# Populated_PLG_sensor.net
KiCad netlist of a schematic drawn in EAGLE
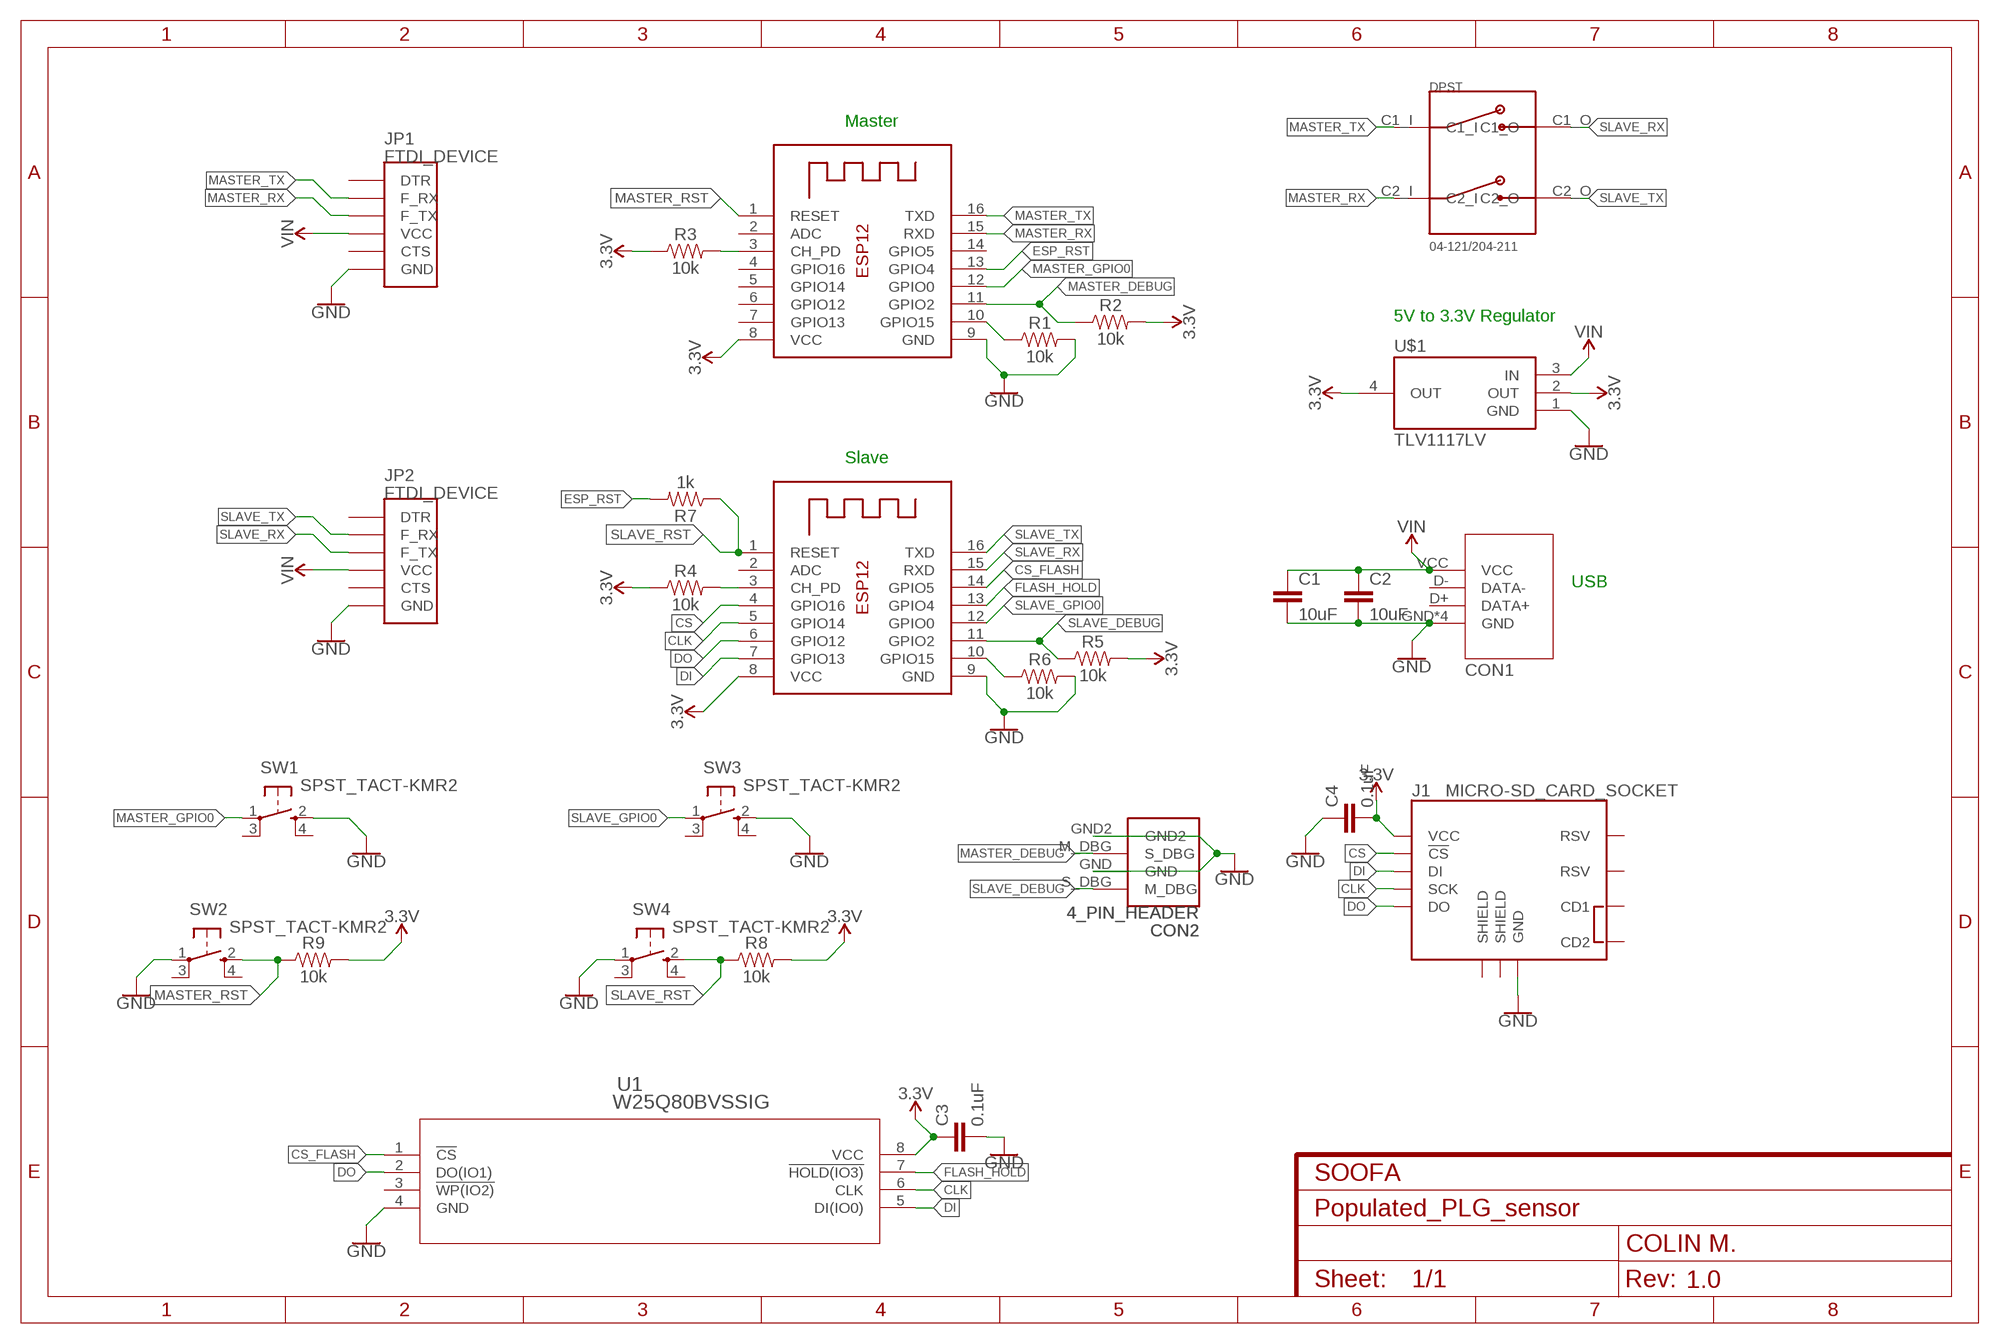
[diagram p0: schematic, sheet 1]

(export (version "E")
  (design (tool "Eeschema 10.0.6"))
  (components
    (comp (ref "C1")
      (value "10uF")
      (footprint "eagle-import:0603")
      (libsource (lib "eagle-import") (part "10UF-0603-6.3V-20%"))
    )
    (comp (ref "C2")
      (value "10uF")
      (footprint "eagle-import:0603")
      (libsource (lib "eagle-import") (part "10UF-0603-6.3V-20%"))
    )
    (comp (ref "C3")
      (value "0.1uF")
      (footprint "eagle-import:0603")
      (libsource (lib "eagle-import") (part "0.1UF-0603-25V-(+80/-20%)"))
    )
    (comp (ref "C4")
      (value "0.1uF")
      (footprint "eagle-import:0603")
      (libsource (lib "eagle-import") (part "0.1UF-0603-25V-(+80/-20%)"))
    )
    (comp (ref "CON1")
      (value "USB_MOLEX_0480372200")
      (footprint "eagle-import:USB_MOLEX_0480372200")
      (libsource (lib "eagle-import") (part "USB_MOLEX_0480372200"))
    )
    (comp (ref "CON2")
      (value "4_PIN_HEADER")
      (footprint "eagle-import:22-23-2041")
      (libsource (lib "eagle-import") (part "4_PIN_HEADER"))
    )
    (comp (ref "DPST1")
      (value "DPST_1POS")
      (footprint "eagle-import:DPST_1POS")
      (libsource (lib "eagle-import") (part "DPST_1POS"))
    )
    (comp (ref "J1")
      (value "MICRO-SD_CARD_SOCKET")
      (footprint "eagle-import:MICRO-SD-SOCKET")
      (libsource (lib "eagle-import") (part "MICRO-SD_CARD_SOCKET"))
    )
    (comp (ref "JP1")
      (value "FTDI_DEVICE")
      (footprint "eagle-import:FTDI_DEVICE_SIDE")
      (libsource (lib "eagle-import") (part "FTDI_DEVICE"))
    )
    (comp (ref "JP2")
      (value "FTDI_DEVICE")
      (footprint "eagle-import:FTDI_DEVICE_SIDE")
      (libsource (lib "eagle-import") (part "FTDI_DEVICE"))
    )
    (comp (ref "R1")
      (value "10k")
      (footprint "eagle-import:0603")
      (libsource (lib "eagle-import") (part "10KOHM-0603-1/10W-1%"))
    )
    (comp (ref "R2")
      (value "10k")
      (footprint "eagle-import:0603")
      (libsource (lib "eagle-import") (part "10KOHM-0603-1/10W-1%"))
    )
    (comp (ref "R3")
      (value "10k")
      (footprint "eagle-import:0603")
      (libsource (lib "eagle-import") (part "10KOHM-0603-1/10W-1%"))
    )
    (comp (ref "R4")
      (value "10k")
      (footprint "eagle-import:0603")
      (libsource (lib "eagle-import") (part "10KOHM-0603-1/10W-1%"))
    )
    (comp (ref "R5")
      (value "10k")
      (footprint "eagle-import:0603")
      (libsource (lib "eagle-import") (part "10KOHM-0603-1/10W-1%"))
    )
    (comp (ref "R6")
      (value "10k")
      (footprint "eagle-import:0603")
      (libsource (lib "eagle-import") (part "10KOHM-0603-1/10W-1%"))
    )
    (comp (ref "R7")
      (value "1k")
      (footprint "eagle-import:0603")
      (libsource (lib "eagle-import") (part "1KOHM-0603-1/10W-1%"))
    )
    (comp (ref "R8")
      (value "10k")
      (footprint "eagle-import:0603")
      (libsource (lib "eagle-import") (part "10KOHM-0603-1/10W-1%"))
    )
    (comp (ref "R9")
      (value "10k")
      (footprint "eagle-import:0603")
      (libsource (lib "eagle-import") (part "10KOHM-0603-1/10W-1%"))
    )
    (comp (ref "SW1")
      (value "SPST_TACT-KMR2")
      (footprint "eagle-import:KMR2")
      (libsource (lib "eagle-import") (part "SPST_TACT-KMR2"))
    )
    (comp (ref "SW2")
      (value "SPST_TACT-KMR2")
      (footprint "eagle-import:KMR2")
      (libsource (lib "eagle-import") (part "SPST_TACT-KMR2"))
    )
    (comp (ref "SW3")
      (value "SPST_TACT-KMR2")
      (footprint "eagle-import:KMR2")
      (libsource (lib "eagle-import") (part "SPST_TACT-KMR2"))
    )
    (comp (ref "SW4")
      (value "SPST_TACT-KMR2")
      (footprint "eagle-import:KMR2")
      (libsource (lib "eagle-import") (part "SPST_TACT-KMR2"))
    )
    (comp (ref "U$1")
      (value "TLV1117LV")
      (footprint "eagle-import:SOT223")
      (libsource (lib "eagle-import") (part "TLV1117LV"))
    )
    (comp (ref "U1")
      (value "W25Q80BVSSIG")
      (footprint "eagle-import:WIN_SS-8")
      (libsource (lib "eagle-import") (part "W25Q80BVSSIG"))
    )
    (comp (ref "X1")
      (value "ESP-12")
      (footprint "eagle-import:ESP-12")
      (libsource (lib "eagle-import") (part "ESP-12"))
    )
    (comp (ref "X2")
      (value "ESP-12")
      (footprint "eagle-import:ESP-12")
      (libsource (lib "eagle-import") (part "ESP-12"))
    )
  )
  (nets
    (net (code "1") (name "3.3V") (class "Default")
      (node (ref "C3") (pin "1") (pinfunction "1_1") (pintype "passive"))
      (node (ref "C4") (pin "2") (pinfunction "2_2") (pintype "passive"))
      (node (ref "J1") (pin "VCC") (pinfunction "VCC_VCC") (pintype "bidirectional"))
      (node (ref "R2") (pin "2") (pinfunction "2_2") (pintype "passive"))
      (node (ref "R3") (pin "1") (pinfunction "1_1") (pintype "passive"))
      (node (ref "R4") (pin "1") (pinfunction "1_1") (pintype "passive"))
      (node (ref "R5") (pin "2") (pinfunction "2_2") (pintype "passive"))
      (node (ref "R8") (pin "2") (pinfunction "2_2") (pintype "passive"))
      (node (ref "R9") (pin "2") (pinfunction "2_2") (pintype "passive"))
      (node (ref "U$1") (pin "2") (pinfunction "OUT_2") (pintype "bidirectional"))
      (node (ref "U$1") (pin "4") (pinfunction "OUT_4") (pintype "bidirectional"))
      (node (ref "U1") (pin "8") (pinfunction "VCC_8") (pintype "power_in"))
      (node (ref "X1") (pin "8") (pinfunction "VCC_8") (pintype "power_in"))
      (node (ref "X2") (pin "8") (pinfunction "VCC_8") (pintype "power_in"))
    )
    (net (code "2") (name "CLK") (class "Default")
      (node (ref "J1") (pin "SCLK") (pinfunction "SCK_SCLK") (pintype "bidirectional"))
      (node (ref "U1") (pin "6") (pinfunction "CLK_6") (pintype "input"))
      (node (ref "X2") (pin "5") (pinfunction "GPIO14_5") (pintype "bidirectional"))
    )
    (net (code "3") (name "CS") (class "Default")
      (node (ref "J1") (pin "CS") (pinfunction "~{CS}_CS") (pintype "bidirectional"))
      (node (ref "X2") (pin "4") (pinfunction "GPIO16_4") (pintype "bidirectional"))
    )
    (net (code "4") (name "CS_FLASH") (class "Default")
      (node (ref "U1") (pin "1") (pinfunction "~{CS}_1") (pintype "input"))
      (node (ref "X2") (pin "14") (pinfunction "GPIO5_14") (pintype "bidirectional"))
    )
    (net (code "5") (name "DI") (class "Default")
      (node (ref "J1") (pin "DI") (pinfunction "DI_DI") (pintype "bidirectional"))
      (node (ref "U1") (pin "5") (pinfunction "DI(IO0)_5") (pintype "bidirectional"))
      (node (ref "X2") (pin "7") (pinfunction "GPIO13_7") (pintype "bidirectional"))
    )
    (net (code "6") (name "DO") (class "Default")
      (node (ref "J1") (pin "DO") (pinfunction "DO_DO") (pintype "bidirectional"))
      (node (ref "U1") (pin "2") (pinfunction "DO(IO1)_2") (pintype "bidirectional"))
      (node (ref "X2") (pin "6") (pinfunction "GPIO12_6") (pintype "bidirectional"))
    )
    (net (code "7") (name "ESP_RST") (class "Default")
      (node (ref "R7") (pin "2") (pinfunction "2_2") (pintype "passive"))
      (node (ref "X1") (pin "13") (pinfunction "GPIO4_13") (pintype "bidirectional"))
    )
    (net (code "8") (name "FLASH_HOLD") (class "Default")
      (node (ref "U1") (pin "7") (pinfunction "~{HOLD(IO3})_7") (pintype "bidirectional"))
      (node (ref "X2") (pin "13") (pinfunction "GPIO4_13") (pintype "bidirectional"))
    )
    (net (code "9") (name "GND") (class "Default")
      (node (ref "C1") (pin "2") (pinfunction "2_2") (pintype "passive"))
      (node (ref "C2") (pin "2") (pinfunction "2_2") (pintype "passive"))
      (node (ref "C3") (pin "2") (pinfunction "2_2") (pintype "passive"))
      (node (ref "C4") (pin "1") (pinfunction "1_1") (pintype "passive"))
      (node (ref "CON1") (pin "GND") (pinfunction "GND_GND") (pintype "bidirectional"))
      (node (ref "CON1") (pin "GND2") (pinfunction "GND_GND2") (pintype "bidirectional"))
      (node (ref "CON1") (pin "GND3") (pinfunction "GND_GND3") (pintype "bidirectional"))
      (node (ref "CON1") (pin "GND4") (pinfunction "GND_GND4") (pintype "bidirectional"))
      (node (ref "CON2") (pin "GND") (pinfunction "GND_GND") (pintype "bidirectional"))
      (node (ref "CON2") (pin "GND2") (pinfunction "GND2_GND2") (pintype "bidirectional"))
      (node (ref "J1") (pin "GND") (pinfunction "GND_GND") (pintype "bidirectional"))
      (node (ref "JP1") (pin "P$6") (pinfunction "GND_P$6") (pintype "bidirectional"))
      (node (ref "JP2") (pin "P$6") (pinfunction "GND_P$6") (pintype "bidirectional"))
      (node (ref "R1") (pin "2") (pinfunction "2_2") (pintype "passive"))
      (node (ref "R6") (pin "2") (pinfunction "2_2") (pintype "passive"))
      (node (ref "SW1") (pin "2") (pinfunction "S_2") (pintype "passive"))
      (node (ref "SW2") (pin "1") (pinfunction "P_1") (pintype "passive"))
      (node (ref "SW3") (pin "2") (pinfunction "S_2") (pintype "passive"))
      (node (ref "SW4") (pin "1") (pinfunction "P_1") (pintype "passive"))
      (node (ref "U$1") (pin "1") (pinfunction "GND_1") (pintype "bidirectional"))
      (node (ref "U1") (pin "4") (pinfunction "GND_4") (pintype "power_in"))
      (node (ref "X1") (pin "9") (pinfunction "GND_9") (pintype "power_in"))
      (node (ref "X2") (pin "9") (pinfunction "GND_9") (pintype "power_in"))
    )
    (net (code "10") (name "MASTER_DEBUG") (class "Default")
      (node (ref "CON2") (pin "M_DBG") (pinfunction "S_DBG_M_DBG") (pintype "bidirectional"))
      (node (ref "R2") (pin "1") (pinfunction "1_1") (pintype "passive"))
      (node (ref "X1") (pin "11") (pinfunction "GPIO2_11") (pintype "bidirectional"))
    )
    (net (code "11") (name "MASTER_GPIO0") (class "Default")
      (node (ref "SW1") (pin "1") (pinfunction "P_1") (pintype "passive"))
      (node (ref "X1") (pin "12") (pinfunction "GPIO0_12") (pintype "bidirectional"))
    )
    (net (code "12") (name "MASTER_RST") (class "Default")
      (node (ref "R9") (pin "1") (pinfunction "1_1") (pintype "passive"))
      (node (ref "SW2") (pin "2") (pinfunction "S_2") (pintype "passive"))
      (node (ref "X1") (pin "1") (pinfunction "RESET_1") (pintype "input"))
    )
    (net (code "13") (name "MASTER_RX") (class "Default")
      (node (ref "DPST1") (pin "C2_I") (pinfunction "C2_I_C2_I") (pintype "bidirectional"))
      (node (ref "JP1") (pin "P$3") (pinfunction "F_TX_P$3") (pintype "bidirectional"))
      (node (ref "X1") (pin "15") (pinfunction "RXD_15") (pintype "input"))
    )
    (net (code "14") (name "MASTER_TX") (class "Default")
      (node (ref "DPST1") (pin "C1_I") (pinfunction "C1_I_C1_I") (pintype "bidirectional"))
      (node (ref "JP1") (pin "P$2") (pinfunction "F_RX_P$2") (pintype "bidirectional"))
      (node (ref "X1") (pin "16") (pinfunction "TXD_16") (pintype "output"))
    )
    (net (code "15") (name "Net-(X1-CH_PD)") (class "Default")
      (node (ref "R3") (pin "2") (pinfunction "2_2") (pintype "passive"))
      (node (ref "X1") (pin "3") (pinfunction "CH_PD_3") (pintype "input"))
    )
    (net (code "16") (name "Net-(X1-GPIO15)") (class "Default")
      (node (ref "R1") (pin "1") (pinfunction "1_1") (pintype "passive"))
      (node (ref "X1") (pin "10") (pinfunction "GPIO15_10") (pintype "bidirectional"))
    )
    (net (code "17") (name "Net-(X2-CH_PD)") (class "Default")
      (node (ref "R4") (pin "2") (pinfunction "2_2") (pintype "passive"))
      (node (ref "X2") (pin "3") (pinfunction "CH_PD_3") (pintype "input"))
    )
    (net (code "18") (name "Net-(X2-GPIO15)") (class "Default")
      (node (ref "R6") (pin "1") (pinfunction "1_1") (pintype "passive"))
      (node (ref "X2") (pin "10") (pinfunction "GPIO15_10") (pintype "bidirectional"))
    )
    (net (code "19") (name "SLAVE_DEBUG") (class "Default")
      (node (ref "CON2") (pin "S_DBG") (pinfunction "M_DBG_S_DBG") (pintype "bidirectional"))
      (node (ref "R5") (pin "1") (pinfunction "1_1") (pintype "passive"))
      (node (ref "X2") (pin "11") (pinfunction "GPIO2_11") (pintype "bidirectional"))
    )
    (net (code "20") (name "SLAVE_GPIO0") (class "Default")
      (node (ref "SW3") (pin "1") (pinfunction "P_1") (pintype "passive"))
      (node (ref "X2") (pin "12") (pinfunction "GPIO0_12") (pintype "bidirectional"))
    )
    (net (code "21") (name "SLAVE_RST") (class "Default")
      (node (ref "R7") (pin "1") (pinfunction "1_1") (pintype "passive"))
      (node (ref "R8") (pin "1") (pinfunction "1_1") (pintype "passive"))
      (node (ref "SW4") (pin "2") (pinfunction "S_2") (pintype "passive"))
      (node (ref "X2") (pin "1") (pinfunction "RESET_1") (pintype "input"))
    )
    (net (code "22") (name "SLAVE_RX") (class "Default")
      (node (ref "DPST1") (pin "C1_O") (pinfunction "C1_O_C1_O") (pintype "bidirectional"))
      (node (ref "JP2") (pin "P$3") (pinfunction "F_TX_P$3") (pintype "bidirectional"))
      (node (ref "X2") (pin "15") (pinfunction "RXD_15") (pintype "input"))
    )
    (net (code "23") (name "SLAVE_TX") (class "Default")
      (node (ref "DPST1") (pin "C2_O") (pinfunction "C2_O_C2_O") (pintype "bidirectional"))
      (node (ref "JP2") (pin "P$2") (pinfunction "F_RX_P$2") (pintype "bidirectional"))
      (node (ref "X2") (pin "16") (pinfunction "TXD_16") (pintype "output"))
    )
    (net (code "24") (name "VIN") (class "Default")
      (node (ref "C1") (pin "1") (pinfunction "1_1") (pintype "passive"))
      (node (ref "C2") (pin "1") (pinfunction "1_1") (pintype "passive"))
      (node (ref "CON1") (pin "VCC") (pinfunction "VCC_VCC") (pintype "bidirectional"))
      (node (ref "JP1") (pin "P$4") (pinfunction "VCC_P$4") (pintype "bidirectional"))
      (node (ref "JP2") (pin "P$4") (pinfunction "VCC_P$4") (pintype "bidirectional"))
      (node (ref "U$1") (pin "3") (pinfunction "IN_3") (pintype "bidirectional"))
    )
    (net (code "25") (name "unconnected-(CON1-DATA+-PadD+)") (class "Default")
      (node (ref "CON1") (pin "D+") (pinfunction "DATA+_D+") (pintype "bidirectional"))
    )
    (net (code "26") (name "unconnected-(CON1-DATA--PadD-)") (class "Default")
      (node (ref "CON1") (pin "D-") (pinfunction "DATA-_D-") (pintype "bidirectional"))
    )
    (net (code "27") (name "unconnected-(J1-PadCD1)") (class "Default")
      (node (ref "J1") (pin "CD1") (pinfunction "CD1_CD1") (pintype "bidirectional"))
    )
    (net (code "28") (name "unconnected-(J1-PadCD2)") (class "Default")
      (node (ref "J1") (pin "CD2") (pinfunction "CD2_CD2") (pintype "bidirectional"))
    )
    (net (code "29") (name "unconnected-(J1-RSV-PadRSV1)") (class "Default")
      (node (ref "J1") (pin "RSV1") (pinfunction "RSV_RSV1") (pintype "bidirectional"))
    )
    (net (code "30") (name "unconnected-(J1-RSV-PadRSV2)") (class "Default")
      (node (ref "J1") (pin "RSV2") (pinfunction "RSV_RSV2") (pintype "bidirectional"))
    )
    (net (code "31") (name "unconnected-(J1-SHIELD-PadGND1)") (class "Default")
      (node (ref "J1") (pin "GND1") (pinfunction "SHIELD_GND1") (pintype "bidirectional"))
    )
    (net (code "32") (name "unconnected-(J1-SHIELD-PadGND3)") (class "Default")
      (node (ref "J1") (pin "GND3") (pinfunction "SHIELD_GND3") (pintype "bidirectional"))
    )
    (net (code "33") (name "unconnected-(JP1-CTS-PadP$5)") (class "Default")
      (node (ref "JP1") (pin "P$5") (pinfunction "CTS_P$5") (pintype "bidirectional"))
    )
    (net (code "34") (name "unconnected-(JP1-DTR-PadP$1)") (class "Default")
      (node (ref "JP1") (pin "P$1") (pinfunction "DTR_P$1") (pintype "bidirectional"))
    )
    (net (code "35") (name "unconnected-(JP2-CTS-PadP$5)") (class "Default")
      (node (ref "JP2") (pin "P$5") (pinfunction "CTS_P$5") (pintype "bidirectional"))
    )
    (net (code "36") (name "unconnected-(JP2-DTR-PadP$1)") (class "Default")
      (node (ref "JP2") (pin "P$1") (pinfunction "DTR_P$1") (pintype "bidirectional"))
    )
    (net (code "37") (name "unconnected-(SW1-P1-Pad3)") (class "Default")
      (node (ref "SW1") (pin "3") (pinfunction "P1_3") (pintype "passive"))
    )
    (net (code "38") (name "unconnected-(SW1-S1-Pad4)") (class "Default")
      (node (ref "SW1") (pin "4") (pinfunction "S1_4") (pintype "passive"))
    )
    (net (code "39") (name "unconnected-(SW2-P1-Pad3)") (class "Default")
      (node (ref "SW2") (pin "3") (pinfunction "P1_3") (pintype "passive"))
    )
    (net (code "40") (name "unconnected-(SW2-S1-Pad4)") (class "Default")
      (node (ref "SW2") (pin "4") (pinfunction "S1_4") (pintype "passive"))
    )
    (net (code "41") (name "unconnected-(SW3-P1-Pad3)") (class "Default")
      (node (ref "SW3") (pin "3") (pinfunction "P1_3") (pintype "passive"))
    )
    (net (code "42") (name "unconnected-(SW3-S1-Pad4)") (class "Default")
      (node (ref "SW3") (pin "4") (pinfunction "S1_4") (pintype "passive"))
    )
    (net (code "43") (name "unconnected-(SW4-P1-Pad3)") (class "Default")
      (node (ref "SW4") (pin "3") (pinfunction "P1_3") (pintype "passive"))
    )
    (net (code "44") (name "unconnected-(SW4-S1-Pad4)") (class "Default")
      (node (ref "SW4") (pin "4") (pinfunction "S1_4") (pintype "passive"))
    )
    (net (code "45") (name "unconnected-(U1-~{WP(IO2})-Pad3)") (class "Default")
      (node (ref "U1") (pin "3") (pinfunction "~{WP(IO2})_3") (pintype "bidirectional"))
    )
    (net (code "46") (name "unconnected-(X1-ADC-Pad2)") (class "Default")
      (node (ref "X1") (pin "2") (pinfunction "ADC_2") (pintype "passive"))
    )
    (net (code "47") (name "unconnected-(X1-GPIO5-Pad14)") (class "Default")
      (node (ref "X1") (pin "14") (pinfunction "GPIO5_14") (pintype "bidirectional"))
    )
    (net (code "48") (name "unconnected-(X1-GPIO12-Pad6)") (class "Default")
      (node (ref "X1") (pin "6") (pinfunction "GPIO12_6") (pintype "bidirectional"))
    )
    (net (code "49") (name "unconnected-(X1-GPIO13-Pad7)") (class "Default")
      (node (ref "X1") (pin "7") (pinfunction "GPIO13_7") (pintype "bidirectional"))
    )
    (net (code "50") (name "unconnected-(X1-GPIO14-Pad5)") (class "Default")
      (node (ref "X1") (pin "5") (pinfunction "GPIO14_5") (pintype "bidirectional"))
    )
    (net (code "51") (name "unconnected-(X1-GPIO16-Pad4)") (class "Default")
      (node (ref "X1") (pin "4") (pinfunction "GPIO16_4") (pintype "bidirectional"))
    )
    (net (code "52") (name "unconnected-(X2-ADC-Pad2)") (class "Default")
      (node (ref "X2") (pin "2") (pinfunction "ADC_2") (pintype "passive"))
    )
  )
)
